# Rangkaian_sensor_GT.net
KiCad netlist of a schematic drawn in EAGLE
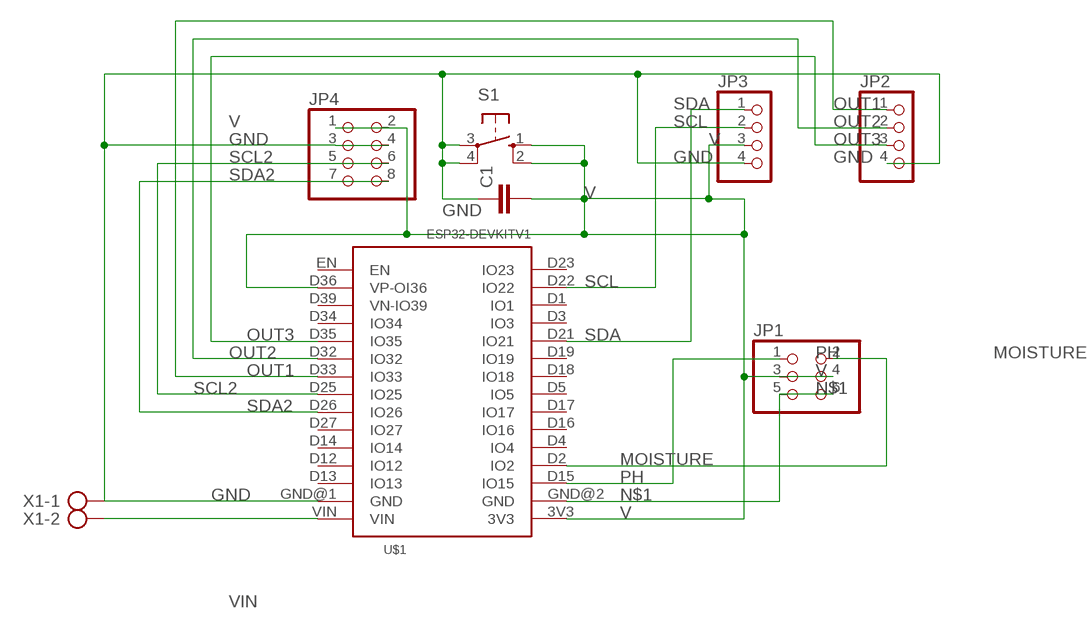
[diagram p0: schematic, sheet 1]

(export (version "E")
  (design (tool "Eeschema 10.0.6"))
  (components
    (comp (ref "C1")
      (value "C-EU050-030X075")
      (footprint "eagle-import:C050-030X075")
      (libsource (lib "eagle-import") (part "C-EU050-030X075"))
    )
    (comp (ref "JP1")
      (value "PINHD-2X3")
      (footprint "eagle-import:2X03")
      (libsource (lib "eagle-import") (part "PINHD-2X3"))
    )
    (comp (ref "JP2")
      (value "PINHD-1X4")
      (footprint "eagle-import:1X04")
      (libsource (lib "eagle-import") (part "PINHD-1X4"))
    )
    (comp (ref "JP3")
      (value "PINHD-1X4")
      (footprint "eagle-import:1X04")
      (libsource (lib "eagle-import") (part "PINHD-1X4"))
    )
    (comp (ref "JP4")
      (value "PINHD-2X4")
      (footprint "eagle-import:2X04")
      (libsource (lib "eagle-import") (part "PINHD-2X4"))
    )
    (comp (ref "S1")
      (value "10-XX")
      (footprint "eagle-import:B3F-10XX")
      (fields (field (name "MPN") "B3F-1000"))
      (libsource (lib "eagle-import") (part "10-XX"))
    )
    (comp (ref "U$1")
      (value "ESP32DEVKITV1")
      (footprint "eagle-import:ESP32-DEVKITV1")
      (libsource (lib "eagle-import") (part "ESP32DEVKITV1"))
    )
    (comp (ref "X1")
      (value "AK300/2")
      (footprint "eagle-import:AK300_2")
      (libsource (lib "eagle-import") (part "AK300/2"))
    )
  )
  (nets
    (net (code "1") (name "/GND") (class "Default")
      (node (ref "C1") (pin "1") (pinfunction "1_1") (pintype "passive"))
      (node (ref "JP2") (pin "4") (pinfunction "4_4") (pintype "passive"))
      (node (ref "JP3") (pin "4") (pinfunction "4_4") (pintype "passive"))
      (node (ref "JP4") (pin "3") (pinfunction "3_3") (pintype "passive"))
      (node (ref "JP4") (pin "4") (pinfunction "4_4") (pintype "passive"))
      (node (ref "S1") (pin "3") (pinfunction "P_3") (pintype "passive"))
      (node (ref "S1") (pin "4") (pinfunction "P1_4") (pintype "passive"))
      (node (ref "U$1") (pin "GND@1") (pinfunction "GND_GND@1") (pintype "bidirectional"))
      (node (ref "X1") (pin "1") (pinfunction "KL_1") (pintype "passive"))
    )
    (net (code "2") (name "/MOISTURE") (class "Default")
      (node (ref "JP1") (pin "2") (pinfunction "2_2") (pintype "passive"))
      (node (ref "U$1") (pin "D2") (pinfunction "IO2_D2") (pintype "bidirectional"))
    )
    (net (code "3") (name "/N$1") (class "Default")
      (node (ref "JP1") (pin "5") (pinfunction "5_5") (pintype "passive"))
      (node (ref "JP1") (pin "6") (pinfunction "6_6") (pintype "passive"))
      (node (ref "U$1") (pin "GND@2") (pinfunction "GND_GND@2") (pintype "bidirectional"))
    )
    (net (code "4") (name "/OUT1") (class "Default")
      (node (ref "JP2") (pin "1") (pinfunction "1_1") (pintype "passive"))
      (node (ref "U$1") (pin "D33") (pinfunction "IO33_D33") (pintype "bidirectional"))
    )
    (net (code "5") (name "/OUT2") (class "Default")
      (node (ref "JP2") (pin "2") (pinfunction "2_2") (pintype "passive"))
      (node (ref "U$1") (pin "D32") (pinfunction "IO32_D32") (pintype "bidirectional"))
    )
    (net (code "6") (name "/OUT3") (class "Default")
      (node (ref "JP2") (pin "3") (pinfunction "3_3") (pintype "passive"))
      (node (ref "U$1") (pin "D35") (pinfunction "IO35_D35") (pintype "bidirectional"))
    )
    (net (code "7") (name "/PH") (class "Default")
      (node (ref "JP1") (pin "1") (pinfunction "1_1") (pintype "passive"))
      (node (ref "U$1") (pin "D15") (pinfunction "IO15_D15") (pintype "bidirectional"))
    )
    (net (code "8") (name "/SCL") (class "Default")
      (node (ref "JP3") (pin "2") (pinfunction "2_2") (pintype "passive"))
      (node (ref "U$1") (pin "D22") (pinfunction "IO22_D22") (pintype "bidirectional"))
    )
    (net (code "9") (name "/SCL2") (class "Default")
      (node (ref "JP4") (pin "5") (pinfunction "5_5") (pintype "passive"))
      (node (ref "JP4") (pin "6") (pinfunction "6_6") (pintype "passive"))
      (node (ref "U$1") (pin "D25") (pinfunction "IO25_D25") (pintype "bidirectional"))
    )
    (net (code "10") (name "/SDA") (class "Default")
      (node (ref "JP3") (pin "1") (pinfunction "1_1") (pintype "passive"))
      (node (ref "U$1") (pin "D21") (pinfunction "IO21_D21") (pintype "bidirectional"))
    )
    (net (code "11") (name "/SDA2") (class "Default")
      (node (ref "JP4") (pin "7") (pinfunction "7_7") (pintype "passive"))
      (node (ref "JP4") (pin "8") (pinfunction "8_8") (pintype "passive"))
      (node (ref "U$1") (pin "D26") (pinfunction "IO26_D26") (pintype "bidirectional"))
    )
    (net (code "12") (name "/V") (class "Default")
      (node (ref "C1") (pin "2") (pinfunction "2_2") (pintype "passive"))
      (node (ref "JP1") (pin "3") (pinfunction "3_3") (pintype "passive"))
      (node (ref "JP1") (pin "4") (pinfunction "4_4") (pintype "passive"))
      (node (ref "JP3") (pin "3") (pinfunction "3_3") (pintype "passive"))
      (node (ref "JP4") (pin "1") (pinfunction "1_1") (pintype "passive"))
      (node (ref "JP4") (pin "2") (pinfunction "2_2") (pintype "passive"))
      (node (ref "S1") (pin "1") (pinfunction "S_1") (pintype "passive"))
      (node (ref "S1") (pin "2") (pinfunction "S1_2") (pintype "passive"))
      (node (ref "U$1") (pin "3V3") (pinfunction "3V3_3V3") (pintype "bidirectional"))
      (node (ref "U$1") (pin "D36") (pinfunction "VP-OI36_D36") (pintype "bidirectional"))
    )
    (net (code "13") (name "/VIN") (class "Default")
      (node (ref "U$1") (pin "VIN") (pinfunction "VIN_VIN") (pintype "bidirectional"))
      (node (ref "X1") (pin "2") (pinfunction "KL_2") (pintype "passive"))
    )
    (net (code "14") (name "unconnected-(U$1-IO1-PadD1)") (class "Default")
      (node (ref "U$1") (pin "D1") (pinfunction "IO1_D1") (pintype "bidirectional"))
    )
    (net (code "15") (name "unconnected-(U$1-IO3-PadD3)") (class "Default")
      (node (ref "U$1") (pin "D3") (pinfunction "IO3_D3") (pintype "bidirectional"))
    )
    (net (code "16") (name "unconnected-(U$1-IO4-PadD4)") (class "Default")
      (node (ref "U$1") (pin "D4") (pinfunction "IO4_D4") (pintype "bidirectional"))
    )
    (net (code "17") (name "unconnected-(U$1-IO5-PadD5)") (class "Default")
      (node (ref "U$1") (pin "D5") (pinfunction "IO5_D5") (pintype "bidirectional"))
    )
    (net (code "18") (name "unconnected-(U$1-IO12-PadD12)") (class "Default")
      (node (ref "U$1") (pin "D12") (pinfunction "IO12_D12") (pintype "bidirectional"))
    )
    (net (code "19") (name "unconnected-(U$1-IO13-PadD13)") (class "Default")
      (node (ref "U$1") (pin "D13") (pinfunction "IO13_D13") (pintype "bidirectional"))
    )
    (net (code "20") (name "unconnected-(U$1-IO14-PadD14)") (class "Default")
      (node (ref "U$1") (pin "D14") (pinfunction "IO14_D14") (pintype "bidirectional"))
    )
    (net (code "21") (name "unconnected-(U$1-IO16-PadD16)") (class "Default")
      (node (ref "U$1") (pin "D16") (pinfunction "IO16_D16") (pintype "bidirectional"))
    )
    (net (code "22") (name "unconnected-(U$1-IO17-PadD17)") (class "Default")
      (node (ref "U$1") (pin "D17") (pinfunction "IO17_D17") (pintype "bidirectional"))
    )
    (net (code "23") (name "unconnected-(U$1-IO18-PadD18)") (class "Default")
      (node (ref "U$1") (pin "D18") (pinfunction "IO18_D18") (pintype "bidirectional"))
    )
    (net (code "24") (name "unconnected-(U$1-IO19-PadD19)") (class "Default")
      (node (ref "U$1") (pin "D19") (pinfunction "IO19_D19") (pintype "bidirectional"))
    )
    (net (code "25") (name "unconnected-(U$1-IO23-PadD23)") (class "Default")
      (node (ref "U$1") (pin "D23") (pinfunction "IO23_D23") (pintype "bidirectional"))
    )
    (net (code "26") (name "unconnected-(U$1-IO27-PadD27)") (class "Default")
      (node (ref "U$1") (pin "D27") (pinfunction "IO27_D27") (pintype "bidirectional"))
    )
    (net (code "27") (name "unconnected-(U$1-IO34-PadD34)") (class "Default")
      (node (ref "U$1") (pin "D34") (pinfunction "IO34_D34") (pintype "bidirectional"))
    )
    (net (code "28") (name "unconnected-(U$1-PadEN)") (class "Default")
      (node (ref "U$1") (pin "EN") (pinfunction "EN_EN") (pintype "bidirectional"))
    )
    (net (code "29") (name "unconnected-(U$1-VN-IO39-PadD39)") (class "Default")
      (node (ref "U$1") (pin "D39") (pinfunction "VN-IO39_D39") (pintype "bidirectional"))
    )
  )
)
